# design.net
KiCad netlist of a schematic drawn in Altium Designer
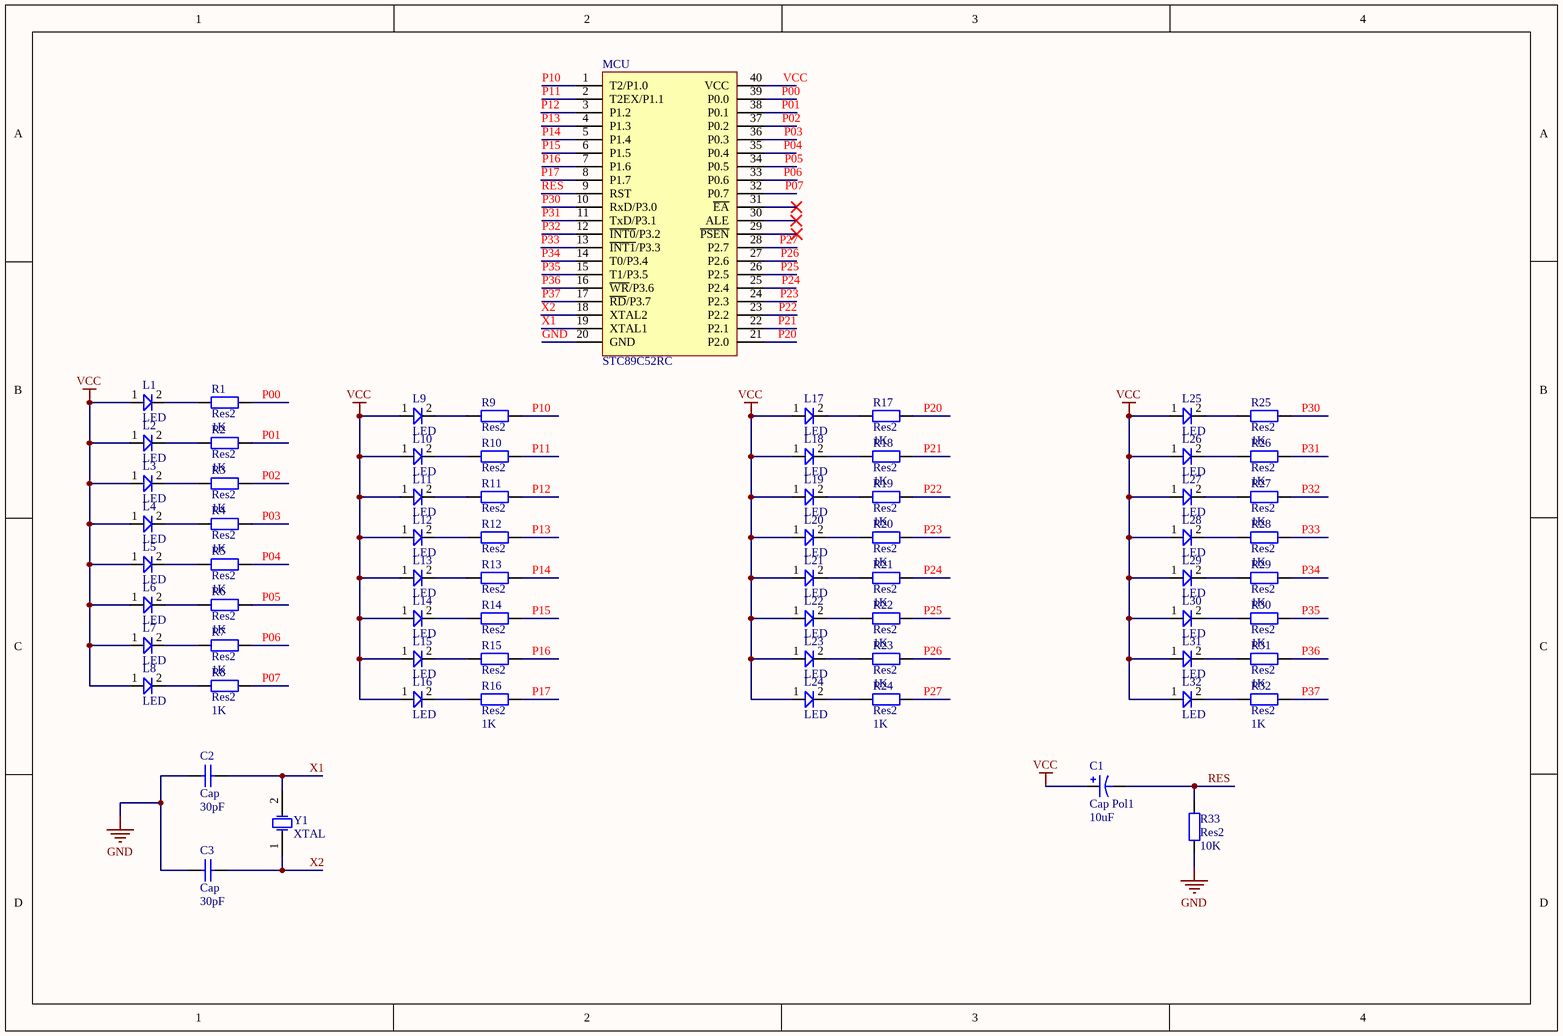
[diagram p0: 心形流水灯原理图.SchDoc]

(export (version "E")
  (design (tool "Eeschema 10.0.6"))
  (components
    (comp (ref "C1")
      (value "Cap Pol1")
      (footprint "CAP-SMD_BD5.0-L5.3-W5.3-FD")
      (description "Polarized Capacitor (Radial)")
      (fields (field (name "ALTIUM_VALUE") "10uF") (field (name "PUBLISHER") "Altium Limited"))
      (libsource (lib "Miscellaneous Devices") (part "Cap Pol1"))
    )
    (comp (ref "C2")
      (value "Cap")
      (footprint "C0603")
      (description "Capacitor")
      (fields (field (name "ALTIUM_VALUE") "30pF") (field (name "PUBLISHER") "Altium Limited"))
      (libsource (lib "Miscellaneous Devices") (part "Cap"))
    )
    (comp (ref "C3")
      (value "Cap")
      (footprint "C0603")
      (description "Capacitor")
      (fields (field (name "ALTIUM_VALUE") "30pF") (field (name "PUBLISHER") "Altium Limited"))
      (libsource (lib "Miscellaneous Devices") (part "Cap"))
    )
    (comp (ref "L1")
      (value "LED")
      (footprint "LED-TH_BD5.6-P2.54-FD")
      (libsource (lib "XIACHUN") (part "LED_T"))
    )
    (comp (ref "L2")
      (value "LED")
      (footprint "LED-TH_BD5.6-P2.54-FD")
      (libsource (lib "XIACHUN") (part "LED_T"))
    )
    (comp (ref "L3")
      (value "LED")
      (footprint "LED-TH_BD5.6-P2.54-FD")
      (libsource (lib "XIACHUN") (part "LED_T"))
    )
    (comp (ref "L4")
      (value "LED")
      (footprint "LED-TH_BD5.6-P2.54-FD")
      (libsource (lib "XIACHUN") (part "LED_T"))
    )
    (comp (ref "L5")
      (value "LED")
      (footprint "LED-TH_BD5.6-P2.54-FD")
      (libsource (lib "XIACHUN") (part "LED_T"))
    )
    (comp (ref "L6")
      (value "LED")
      (footprint "LED-TH_BD5.6-P2.54-FD")
      (libsource (lib "XIACHUN") (part "LED_T"))
    )
    (comp (ref "L7")
      (value "LED")
      (footprint "LED-TH_BD5.6-P2.54-FD")
      (libsource (lib "XIACHUN") (part "LED_T"))
    )
    (comp (ref "L8")
      (value "LED")
      (footprint "LED-TH_BD5.6-P2.54-FD")
      (libsource (lib "XIACHUN") (part "LED_T"))
    )
    (comp (ref "L9")
      (value "LED")
      (footprint "LED-TH_BD5.6-P2.54-FD")
      (libsource (lib "XIACHUN") (part "LED_T"))
    )
    (comp (ref "L10")
      (value "LED")
      (footprint "LED-TH_BD5.6-P2.54-FD")
      (libsource (lib "XIACHUN") (part "LED_T"))
    )
    (comp (ref "L11")
      (value "LED")
      (footprint "LED-TH_BD5.6-P2.54-FD")
      (libsource (lib "XIACHUN") (part "LED_T"))
    )
    (comp (ref "L12")
      (value "LED")
      (footprint "LED-TH_BD5.6-P2.54-FD")
      (libsource (lib "XIACHUN") (part "LED_T"))
    )
    (comp (ref "L13")
      (value "LED")
      (footprint "LED-TH_BD5.6-P2.54-FD")
      (libsource (lib "XIACHUN") (part "LED_T"))
    )
    (comp (ref "L14")
      (value "LED")
      (footprint "LED-TH_BD5.6-P2.54-FD")
      (libsource (lib "XIACHUN") (part "LED_T"))
    )
    (comp (ref "L15")
      (value "LED")
      (footprint "LED-TH_BD5.6-P2.54-FD")
      (libsource (lib "XIACHUN") (part "LED_T"))
    )
    (comp (ref "L16")
      (value "LED")
      (footprint "LED-TH_BD5.6-P2.54-FD")
      (libsource (lib "XIACHUN") (part "LED_T"))
    )
    (comp (ref "L17")
      (value "LED")
      (footprint "LED-TH_BD5.6-P2.54-FD")
      (libsource (lib "XIACHUN") (part "LED_T"))
    )
    (comp (ref "L18")
      (value "LED")
      (footprint "LED-TH_BD5.6-P2.54-FD")
      (libsource (lib "XIACHUN") (part "LED_T"))
    )
    (comp (ref "L19")
      (value "LED")
      (footprint "LED-TH_BD5.6-P2.54-FD")
      (libsource (lib "XIACHUN") (part "LED_T"))
    )
    (comp (ref "L20")
      (value "LED")
      (footprint "LED-TH_BD5.6-P2.54-FD")
      (libsource (lib "XIACHUN") (part "LED_T"))
    )
    (comp (ref "L21")
      (value "LED")
      (footprint "LED-TH_BD5.6-P2.54-FD")
      (libsource (lib "XIACHUN") (part "LED_T"))
    )
    (comp (ref "L22")
      (value "LED")
      (footprint "LED-TH_BD5.6-P2.54-FD")
      (libsource (lib "XIACHUN") (part "LED_T"))
    )
    (comp (ref "L23")
      (value "LED")
      (footprint "LED-TH_BD5.6-P2.54-FD")
      (libsource (lib "XIACHUN") (part "LED_T"))
    )
    (comp (ref "L24")
      (value "LED")
      (footprint "LED-TH_BD5.6-P2.54-FD")
      (libsource (lib "XIACHUN") (part "LED_T"))
    )
    (comp (ref "L25")
      (value "LED")
      (footprint "LED-TH_BD5.6-P2.54-FD")
      (libsource (lib "XIACHUN") (part "LED_T"))
    )
    (comp (ref "L26")
      (value "LED")
      (footprint "LED-TH_BD5.6-P2.54-FD")
      (libsource (lib "XIACHUN") (part "LED_T"))
    )
    (comp (ref "L27")
      (value "LED")
      (footprint "LED-TH_BD5.6-P2.54-FD")
      (libsource (lib "XIACHUN") (part "LED_T"))
    )
    (comp (ref "L28")
      (value "LED")
      (footprint "LED-TH_BD5.6-P2.54-FD")
      (libsource (lib "XIACHUN") (part "LED_T"))
    )
    (comp (ref "L29")
      (value "LED")
      (footprint "LED-TH_BD5.6-P2.54-FD")
      (libsource (lib "XIACHUN") (part "LED_T"))
    )
    (comp (ref "L30")
      (value "LED")
      (footprint "LED-TH_BD5.6-P2.54-FD")
      (libsource (lib "XIACHUN") (part "LED_T"))
    )
    (comp (ref "L31")
      (value "LED")
      (footprint "LED-TH_BD5.6-P2.54-FD")
      (libsource (lib "XIACHUN") (part "LED_T"))
    )
    (comp (ref "L32")
      (value "LED")
      (footprint "LED-TH_BD5.6-P2.54-FD")
      (libsource (lib "XIACHUN") (part "LED_T"))
    )
    (comp (ref "MCU")
      (value "STC89C52RC")
      (footprint "DIP-40_L50.8-W17.8-P2.54-LS15.2-BL")
      (description "STC单片机")
      (fields (field (name "版权归属") "源创客"))
      (libsource (lib "STC系列单片机") (part "STC89C52RC"))
    )
    (comp (ref "R1")
      (value "Res2")
      (footprint "R0603")
      (description "Resistor")
      (fields (field (name "ALTIUM_VALUE") "1K") (field (name "PUBLISHER") "Altium Limited"))
      (libsource (lib "Miscellaneous Devices") (part "Res2"))
    )
    (comp (ref "R2")
      (value "Res2")
      (footprint "R0603")
      (description "Resistor")
      (fields (field (name "ALTIUM_VALUE") "1K") (field (name "PUBLISHER") "Altium Limited"))
      (libsource (lib "Miscellaneous Devices") (part "Res2"))
    )
    (comp (ref "R3")
      (value "Res2")
      (footprint "R0603")
      (description "Resistor")
      (fields (field (name "ALTIUM_VALUE") "1K") (field (name "PUBLISHER") "Altium Limited"))
      (libsource (lib "Miscellaneous Devices") (part "Res2"))
    )
    (comp (ref "R4")
      (value "Res2")
      (footprint "R0603")
      (description "Resistor")
      (fields (field (name "ALTIUM_VALUE") "1K") (field (name "PUBLISHER") "Altium Limited"))
      (libsource (lib "Miscellaneous Devices") (part "Res2"))
    )
    (comp (ref "R5")
      (value "Res2")
      (footprint "R0603")
      (description "Resistor")
      (fields (field (name "ALTIUM_VALUE") "1K") (field (name "PUBLISHER") "Altium Limited"))
      (libsource (lib "Miscellaneous Devices") (part "Res2"))
    )
    (comp (ref "R6")
      (value "Res2")
      (footprint "R0603")
      (description "Resistor")
      (fields (field (name "ALTIUM_VALUE") "1K") (field (name "PUBLISHER") "Altium Limited"))
      (libsource (lib "Miscellaneous Devices") (part "Res2"))
    )
    (comp (ref "R7")
      (value "Res2")
      (footprint "R0603")
      (description "Resistor")
      (fields (field (name "ALTIUM_VALUE") "1K") (field (name "PUBLISHER") "Altium Limited"))
      (libsource (lib "Miscellaneous Devices") (part "Res2"))
    )
    (comp (ref "R8")
      (value "Res2")
      (footprint "R0603")
      (description "Resistor")
      (fields (field (name "ALTIUM_VALUE") "1K") (field (name "PUBLISHER") "Altium Limited"))
      (libsource (lib "Miscellaneous Devices") (part "Res2"))
    )
    (comp (ref "R9")
      (value "Res2")
      (footprint "R0603")
      (description "Resistor")
      (fields (field (name "PUBLISHER") "Altium Limited"))
      (libsource (lib "Miscellaneous Devices") (part "Res2"))
    )
    (comp (ref "R10")
      (value "Res2")
      (footprint "R0603")
      (description "Resistor")
      (fields (field (name "PUBLISHER") "Altium Limited"))
      (libsource (lib "Miscellaneous Devices") (part "Res2"))
    )
    (comp (ref "R11")
      (value "Res2")
      (footprint "R0603")
      (description "Resistor")
      (fields (field (name "PUBLISHER") "Altium Limited"))
      (libsource (lib "Miscellaneous Devices") (part "Res2"))
    )
    (comp (ref "R12")
      (value "Res2")
      (footprint "R0603")
      (description "Resistor")
      (fields (field (name "PUBLISHER") "Altium Limited"))
      (libsource (lib "Miscellaneous Devices") (part "Res2"))
    )
    (comp (ref "R13")
      (value "Res2")
      (footprint "R0603")
      (description "Resistor")
      (fields (field (name "PUBLISHER") "Altium Limited"))
      (libsource (lib "Miscellaneous Devices") (part "Res2"))
    )
    (comp (ref "R14")
      (value "Res2")
      (footprint "R0603")
      (description "Resistor")
      (fields (field (name "PUBLISHER") "Altium Limited"))
      (libsource (lib "Miscellaneous Devices") (part "Res2"))
    )
    (comp (ref "R15")
      (value "Res2")
      (footprint "R0603")
      (description "Resistor")
      (fields (field (name "PUBLISHER") "Altium Limited"))
      (libsource (lib "Miscellaneous Devices") (part "Res2"))
    )
    (comp (ref "R16")
      (value "Res2")
      (footprint "R0603")
      (description "Resistor")
      (fields (field (name "ALTIUM_VALUE") "1K") (field (name "PUBLISHER") "Altium Limited"))
      (libsource (lib "Miscellaneous Devices") (part "Res2"))
    )
    (comp (ref "R17")
      (value "Res2")
      (footprint "R0603")
      (description "Resistor")
      (fields (field (name "ALTIUM_VALUE") "1K") (field (name "PUBLISHER") "Altium Limited"))
      (libsource (lib "Miscellaneous Devices") (part "Res2"))
    )
    (comp (ref "R18")
      (value "Res2")
      (footprint "R0603")
      (description "Resistor")
      (fields (field (name "ALTIUM_VALUE") "1K") (field (name "PUBLISHER") "Altium Limited"))
      (libsource (lib "Miscellaneous Devices") (part "Res2"))
    )
    (comp (ref "R19")
      (value "Res2")
      (footprint "R0603")
      (description "Resistor")
      (fields (field (name "ALTIUM_VALUE") "1K") (field (name "PUBLISHER") "Altium Limited"))
      (libsource (lib "Miscellaneous Devices") (part "Res2"))
    )
    (comp (ref "R20")
      (value "Res2")
      (footprint "R0603")
      (description "Resistor")
      (fields (field (name "ALTIUM_VALUE") "1K") (field (name "PUBLISHER") "Altium Limited"))
      (libsource (lib "Miscellaneous Devices") (part "Res2"))
    )
    (comp (ref "R21")
      (value "Res2")
      (footprint "R0603")
      (description "Resistor")
      (fields (field (name "ALTIUM_VALUE") "1K") (field (name "PUBLISHER") "Altium Limited"))
      (libsource (lib "Miscellaneous Devices") (part "Res2"))
    )
    (comp (ref "R22")
      (value "Res2")
      (footprint "R0603")
      (description "Resistor")
      (fields (field (name "ALTIUM_VALUE") "1K") (field (name "PUBLISHER") "Altium Limited"))
      (libsource (lib "Miscellaneous Devices") (part "Res2"))
    )
    (comp (ref "R23")
      (value "Res2")
      (footprint "R0603")
      (description "Resistor")
      (fields (field (name "ALTIUM_VALUE") "1K") (field (name "PUBLISHER") "Altium Limited"))
      (libsource (lib "Miscellaneous Devices") (part "Res2"))
    )
    (comp (ref "R24")
      (value "Res2")
      (footprint "R0603")
      (description "Resistor")
      (fields (field (name "ALTIUM_VALUE") "1K") (field (name "PUBLISHER") "Altium Limited"))
      (libsource (lib "Miscellaneous Devices") (part "Res2"))
    )
    (comp (ref "R25")
      (value "Res2")
      (footprint "R0603")
      (description "Resistor")
      (fields (field (name "ALTIUM_VALUE") "1K") (field (name "PUBLISHER") "Altium Limited"))
      (libsource (lib "Miscellaneous Devices") (part "Res2"))
    )
    (comp (ref "R26")
      (value "Res2")
      (footprint "R0603")
      (description "Resistor")
      (fields (field (name "ALTIUM_VALUE") "1K") (field (name "PUBLISHER") "Altium Limited"))
      (libsource (lib "Miscellaneous Devices") (part "Res2"))
    )
    (comp (ref "R27")
      (value "Res2")
      (footprint "R0603")
      (description "Resistor")
      (fields (field (name "ALTIUM_VALUE") "1K") (field (name "PUBLISHER") "Altium Limited"))
      (libsource (lib "Miscellaneous Devices") (part "Res2"))
    )
    (comp (ref "R28")
      (value "Res2")
      (footprint "R0603")
      (description "Resistor")
      (fields (field (name "ALTIUM_VALUE") "1K") (field (name "PUBLISHER") "Altium Limited"))
      (libsource (lib "Miscellaneous Devices") (part "Res2"))
    )
    (comp (ref "R29")
      (value "Res2")
      (footprint "R0603")
      (description "Resistor")
      (fields (field (name "ALTIUM_VALUE") "1K") (field (name "PUBLISHER") "Altium Limited"))
      (libsource (lib "Miscellaneous Devices") (part "Res2"))
    )
    (comp (ref "R30")
      (value "Res2")
      (footprint "R0603")
      (description "Resistor")
      (fields (field (name "ALTIUM_VALUE") "1K") (field (name "PUBLISHER") "Altium Limited"))
      (libsource (lib "Miscellaneous Devices") (part "Res2"))
    )
    (comp (ref "R31")
      (value "Res2")
      (footprint "R0603")
      (description "Resistor")
      (fields (field (name "ALTIUM_VALUE") "1K") (field (name "PUBLISHER") "Altium Limited"))
      (libsource (lib "Miscellaneous Devices") (part "Res2"))
    )
    (comp (ref "R32")
      (value "Res2")
      (footprint "R0603")
      (description "Resistor")
      (fields (field (name "ALTIUM_VALUE") "1K") (field (name "PUBLISHER") "Altium Limited"))
      (libsource (lib "Miscellaneous Devices") (part "Res2"))
    )
    (comp (ref "R33")
      (value "Res2")
      (footprint "R0603")
      (description "Resistor")
      (fields (field (name "ALTIUM_VALUE") "10K") (field (name "PUBLISHER") "Altium Limited"))
      (libsource (lib "") (part "Res2_1"))
    )
    (comp (ref "Y1")
      (value "XTAL")
      (footprint "HC-49S_L11.4-W4.8")
      (description "Crystal Oscillator")
      (fields (field (name "PUBLISHER") "Altium Limited"))
      (libsource (lib "Miscellaneous Devices") (part "XTAL"))
    )
  )
  (nets
    (net (code "1") (name "/P00") (class "Default")
      (node (ref "MCU") (pin "39") (pinfunction "P0.0_39") (pintype "passive"))
      (node (ref "R1") (pin "2") (pinfunction "2_2") (pintype "passive"))
    )
    (net (code "2") (name "/P01") (class "Default")
      (node (ref "MCU") (pin "38") (pinfunction "P0.1_38") (pintype "passive"))
      (node (ref "R2") (pin "2") (pinfunction "2_2") (pintype "passive"))
    )
    (net (code "3") (name "/P02") (class "Default")
      (node (ref "MCU") (pin "37") (pinfunction "P0.2_37") (pintype "passive"))
      (node (ref "R3") (pin "2") (pinfunction "2_2") (pintype "passive"))
    )
    (net (code "4") (name "/P03") (class "Default")
      (node (ref "MCU") (pin "36") (pinfunction "P0.3_36") (pintype "passive"))
      (node (ref "R4") (pin "2") (pinfunction "2_2") (pintype "passive"))
    )
    (net (code "5") (name "/P04") (class "Default")
      (node (ref "MCU") (pin "35") (pinfunction "P0.4_35") (pintype "passive"))
      (node (ref "R5") (pin "2") (pinfunction "2_2") (pintype "passive"))
    )
    (net (code "6") (name "/P05") (class "Default")
      (node (ref "MCU") (pin "34") (pinfunction "P0.5_34") (pintype "passive"))
      (node (ref "R6") (pin "2") (pinfunction "2_2") (pintype "passive"))
    )
    (net (code "7") (name "/P06") (class "Default")
      (node (ref "MCU") (pin "33") (pinfunction "P0.6_33") (pintype "passive"))
      (node (ref "R7") (pin "2") (pinfunction "2_2") (pintype "passive"))
    )
    (net (code "8") (name "/P07") (class "Default")
      (node (ref "MCU") (pin "32") (pinfunction "P0.7_32") (pintype "passive"))
      (node (ref "R8") (pin "2") (pinfunction "2_2") (pintype "passive"))
    )
    (net (code "9") (name "/P10") (class "Default")
      (node (ref "MCU") (pin "1") (pinfunction "T2/P1.0_1") (pintype "passive"))
      (node (ref "R9") (pin "2") (pinfunction "2_2") (pintype "passive"))
    )
    (net (code "10") (name "/P11") (class "Default")
      (node (ref "MCU") (pin "2") (pinfunction "T2EX/P1.1_2") (pintype "passive"))
      (node (ref "R10") (pin "2") (pinfunction "2_2") (pintype "passive"))
    )
    (net (code "11") (name "/P12") (class "Default")
      (node (ref "MCU") (pin "3") (pinfunction "P1.2_3") (pintype "passive"))
      (node (ref "R11") (pin "2") (pinfunction "2_2") (pintype "passive"))
    )
    (net (code "12") (name "/P13") (class "Default")
      (node (ref "MCU") (pin "4") (pinfunction "P1.3_4") (pintype "passive"))
      (node (ref "R12") (pin "2") (pinfunction "2_2") (pintype "passive"))
    )
    (net (code "13") (name "/P14") (class "Default")
      (node (ref "MCU") (pin "5") (pinfunction "P1.4_5") (pintype "passive"))
      (node (ref "R13") (pin "2") (pinfunction "2_2") (pintype "passive"))
    )
    (net (code "14") (name "/P15") (class "Default")
      (node (ref "MCU") (pin "6") (pinfunction "P1.5_6") (pintype "passive"))
      (node (ref "R14") (pin "2") (pinfunction "2_2") (pintype "passive"))
    )
    (net (code "15") (name "/P16") (class "Default")
      (node (ref "MCU") (pin "7") (pinfunction "P1.6_7") (pintype "passive"))
      (node (ref "R15") (pin "2") (pinfunction "2_2") (pintype "passive"))
    )
    (net (code "16") (name "/P17") (class "Default")
      (node (ref "MCU") (pin "8") (pinfunction "P1.7_8") (pintype "passive"))
      (node (ref "R16") (pin "2") (pinfunction "2_2") (pintype "passive"))
    )
    (net (code "17") (name "/P20") (class "Default")
      (node (ref "MCU") (pin "21") (pinfunction "P2.0_21") (pintype "passive"))
      (node (ref "R17") (pin "2") (pinfunction "2_2") (pintype "passive"))
    )
    (net (code "18") (name "/P21") (class "Default")
      (node (ref "MCU") (pin "22") (pinfunction "P2.1_22") (pintype "passive"))
      (node (ref "R18") (pin "2") (pinfunction "2_2") (pintype "passive"))
    )
    (net (code "19") (name "/P22") (class "Default")
      (node (ref "MCU") (pin "23") (pinfunction "P2.2_23") (pintype "passive"))
      (node (ref "R19") (pin "2") (pinfunction "2_2") (pintype "passive"))
    )
    (net (code "20") (name "/P23") (class "Default")
      (node (ref "MCU") (pin "24") (pinfunction "P2.3_24") (pintype "passive"))
      (node (ref "R20") (pin "2") (pinfunction "2_2") (pintype "passive"))
    )
    (net (code "21") (name "/P24") (class "Default")
      (node (ref "MCU") (pin "25") (pinfunction "P2.4_25") (pintype "passive"))
      (node (ref "R21") (pin "2") (pinfunction "2_2") (pintype "passive"))
    )
    (net (code "22") (name "/P25") (class "Default")
      (node (ref "MCU") (pin "26") (pinfunction "P2.5_26") (pintype "passive"))
      (node (ref "R22") (pin "2") (pinfunction "2_2") (pintype "passive"))
    )
    (net (code "23") (name "/P26") (class "Default")
      (node (ref "MCU") (pin "27") (pinfunction "P2.6_27") (pintype "passive"))
      (node (ref "R23") (pin "2") (pinfunction "2_2") (pintype "passive"))
    )
    (net (code "24") (name "/P27") (class "Default")
      (node (ref "MCU") (pin "28") (pinfunction "P2.7_28") (pintype "passive"))
      (node (ref "R24") (pin "2") (pinfunction "2_2") (pintype "passive"))
    )
    (net (code "25") (name "/P30") (class "Default")
      (node (ref "MCU") (pin "10") (pinfunction "RxD/P3.0_10") (pintype "passive"))
      (node (ref "R25") (pin "2") (pinfunction "2_2") (pintype "passive"))
    )
    (net (code "26") (name "/P31") (class "Default")
      (node (ref "MCU") (pin "11") (pinfunction "TxD/P3.1_11") (pintype "passive"))
      (node (ref "R26") (pin "2") (pinfunction "2_2") (pintype "passive"))
    )
    (net (code "27") (name "/P32") (class "Default")
      (node (ref "MCU") (pin "12") (pinfunction "~{INT0}/P3.2_12") (pintype "passive"))
      (node (ref "R27") (pin "2") (pinfunction "2_2") (pintype "passive"))
    )
    (net (code "28") (name "/P33") (class "Default")
      (node (ref "MCU") (pin "13") (pinfunction "~{INT1}/P3.3_13") (pintype "passive"))
      (node (ref "R28") (pin "2") (pinfunction "2_2") (pintype "passive"))
    )
    (net (code "29") (name "/P34") (class "Default")
      (node (ref "MCU") (pin "14") (pinfunction "T0/P3.4_14") (pintype "passive"))
      (node (ref "R29") (pin "2") (pinfunction "2_2") (pintype "passive"))
    )
    (net (code "30") (name "/P35") (class "Default")
      (node (ref "MCU") (pin "15") (pinfunction "T1/P3.5_15") (pintype "passive"))
      (node (ref "R30") (pin "2") (pinfunction "2_2") (pintype "passive"))
    )
    (net (code "31") (name "/P36") (class "Default")
      (node (ref "MCU") (pin "16") (pinfunction "~{WR}/P3.6_16") (pintype "passive"))
      (node (ref "R31") (pin "2") (pinfunction "2_2") (pintype "passive"))
    )
    (net (code "32") (name "/P37") (class "Default")
      (node (ref "MCU") (pin "17") (pinfunction "~{RD}/P3.7_17") (pintype "passive"))
      (node (ref "R32") (pin "2") (pinfunction "2_2") (pintype "passive"))
    )
    (net (code "33") (name "/RES") (class "Default")
      (node (ref "C1") (pin "2") (pinfunction "2_2") (pintype "passive"))
      (node (ref "MCU") (pin "9") (pinfunction "RST_9") (pintype "passive"))
      (node (ref "R33") (pin "2") (pinfunction "2_2") (pintype "passive"))
    )
    (net (code "34") (name "/X1") (class "Default")
      (node (ref "C2") (pin "2") (pinfunction "2_2") (pintype "passive"))
      (node (ref "MCU") (pin "19") (pinfunction "XTAL1_19") (pintype "passive"))
      (node (ref "Y1") (pin "2") (pinfunction "OSC2_2") (pintype "passive"))
    )
    (net (code "35") (name "/X2") (class "Default")
      (node (ref "C3") (pin "2") (pinfunction "2_2") (pintype "passive"))
      (node (ref "MCU") (pin "18") (pinfunction "XTAL2_18") (pintype "passive"))
      (node (ref "Y1") (pin "1") (pinfunction "OSC1_1") (pintype "passive"))
    )
    (net (code "36") (name "GND") (class "Default")
      (node (ref "C2") (pin "1") (pinfunction "1_1") (pintype "passive"))
      (node (ref "C3") (pin "1") (pinfunction "1_1") (pintype "passive"))
      (node (ref "MCU") (pin "20") (pinfunction "GND_20") (pintype "passive"))
      (node (ref "R33") (pin "1") (pinfunction "1_1") (pintype "passive"))
    )
    (net (code "37") (name "Net-(L1-Pad2)") (class "Default")
      (node (ref "L1") (pin "2") (pinfunction "2_2") (pintype "passive"))
      (node (ref "R1") (pin "1") (pinfunction "1_1") (pintype "passive"))
    )
    (net (code "38") (name "Net-(L2-Pad2)") (class "Default")
      (node (ref "L2") (pin "2") (pinfunction "2_2") (pintype "passive"))
      (node (ref "R2") (pin "1") (pinfunction "1_1") (pintype "passive"))
    )
    (net (code "39") (name "Net-(L3-Pad2)") (class "Default")
      (node (ref "L3") (pin "2") (pinfunction "2_2") (pintype "passive"))
      (node (ref "R3") (pin "1") (pinfunction "1_1") (pintype "passive"))
    )
    (net (code "40") (name "Net-(L4-Pad2)") (class "Default")
      (node (ref "L4") (pin "2") (pinfunction "2_2") (pintype "passive"))
      (node (ref "R4") (pin "1") (pinfunction "1_1") (pintype "passive"))
    )
    (net (code "41") (name "Net-(L5-Pad2)") (class "Default")
      (node (ref "L5") (pin "2") (pinfunction "2_2") (pintype "passive"))
      (node (ref "R5") (pin "1") (pinfunction "1_1") (pintype "passive"))
    )
    (net (code "42") (name "Net-(L6-Pad2)") (class "Default")
      (node (ref "L6") (pin "2") (pinfunction "2_2") (pintype "passive"))
      (node (ref "R6") (pin "1") (pinfunction "1_1") (pintype "passive"))
    )
    (net (code "43") (name "Net-(L7-Pad2)") (class "Default")
      (node (ref "L7") (pin "2") (pinfunction "2_2") (pintype "passive"))
      (node (ref "R7") (pin "1") (pinfunction "1_1") (pintype "passive"))
    )
    (net (code "44") (name "Net-(L8-Pad2)") (class "Default")
      (node (ref "L8") (pin "2") (pinfunction "2_2") (pintype "passive"))
      (node (ref "R8") (pin "1") (pinfunction "1_1") (pintype "passive"))
    )
    (net (code "45") (name "Net-(L9-Pad2)") (class "Default")
      (node (ref "L9") (pin "2") (pinfunction "2_2") (pintype "passive"))
      (node (ref "R9") (pin "1") (pinfunction "1_1") (pintype "passive"))
    )
    (net (code "46") (name "Net-(L10-Pad2)") (class "Default")
      (node (ref "L10") (pin "2") (pinfunction "2_2") (pintype "passive"))
      (node (ref "R10") (pin "1") (pinfunction "1_1") (pintype "passive"))
    )
    (net (code "47") (name "Net-(L11-Pad2)") (class "Default")
      (node (ref "L11") (pin "2") (pinfunction "2_2") (pintype "passive"))
      (node (ref "R11") (pin "1") (pinfunction "1_1") (pintype "passive"))
    )
    (net (code "48") (name "Net-(L12-Pad2)") (class "Default")
      (node (ref "L12") (pin "2") (pinfunction "2_2") (pintype "passive"))
      (node (ref "R12") (pin "1") (pinfunction "1_1") (pintype "passive"))
    )
    (net (code "49") (name "Net-(L13-Pad2)") (class "Default")
      (node (ref "L13") (pin "2") (pinfunction "2_2") (pintype "passive"))
      (node (ref "R13") (pin "1") (pinfunction "1_1") (pintype "passive"))
    )
    (net (code "50") (name "Net-(L14-Pad2)") (class "Default")
      (node (ref "L14") (pin "2") (pinfunction "2_2") (pintype "passive"))
      (node (ref "R14") (pin "1") (pinfunction "1_1") (pintype "passive"))
    )
    (net (code "51") (name "Net-(L15-Pad2)") (class "Default")
      (node (ref "L15") (pin "2") (pinfunction "2_2") (pintype "passive"))
      (node (ref "R15") (pin "1") (pinfunction "1_1") (pintype "passive"))
    )
    (net (code "52") (name "Net-(L16-Pad2)") (class "Default")
      (node (ref "L16") (pin "2") (pinfunction "2_2") (pintype "passive"))
      (node (ref "R16") (pin "1") (pinfunction "1_1") (pintype "passive"))
    )
    (net (code "53") (name "Net-(L17-Pad2)") (class "Default")
      (node (ref "L17") (pin "2") (pinfunction "2_2") (pintype "passive"))
      (node (ref "R17") (pin "1") (pinfunction "1_1") (pintype "passive"))
    )
    (net (code "54") (name "Net-(L18-Pad2)") (class "Default")
      (node (ref "L18") (pin "2") (pinfunction "2_2") (pintype "passive"))
      (node (ref "R18") (pin "1") (pinfunction "1_1") (pintype "passive"))
    )
    (net (code "55") (name "Net-(L19-Pad2)") (class "Default")
      (node (ref "L19") (pin "2") (pinfunction "2_2") (pintype "passive"))
      (node (ref "R19") (pin "1") (pinfunction "1_1") (pintype "passive"))
    )
    (net (code "56") (name "Net-(L20-Pad2)") (class "Default")
      (node (ref "L20") (pin "2") (pinfunction "2_2") (pintype "passive"))
      (node (ref "R20") (pin "1") (pinfunction "1_1") (pintype "passive"))
    )
    (net (code "57") (name "Net-(L21-Pad2)") (class "Default")
      (node (ref "L21") (pin "2") (pinfunction "2_2") (pintype "passive"))
      (node (ref "R21") (pin "1") (pinfunction "1_1") (pintype "passive"))
    )
    (net (code "58") (name "Net-(L22-Pad2)") (class "Default")
      (node (ref "L22") (pin "2") (pinfunction "2_2") (pintype "passive"))
      (node (ref "R22") (pin "1") (pinfunction "1_1") (pintype "passive"))
    )
    (net (code "59") (name "Net-(L23-Pad2)") (class "Default")
      (node (ref "L23") (pin "2") (pinfunction "2_2") (pintype "passive"))
      (node (ref "R23") (pin "1") (pinfunction "1_1") (pintype "passive"))
    )
    (net (code "60") (name "Net-(L24-Pad2)") (class "Default")
      (node (ref "L24") (pin "2") (pinfunction "2_2") (pintype "passive"))
      (node (ref "R24") (pin "1") (pinfunction "1_1") (pintype "passive"))
    )
    (net (code "61") (name "Net-(L25-Pad2)") (class "Default")
      (node (ref "L25") (pin "2") (pinfunction "2_2") (pintype "passive"))
      (node (ref "R25") (pin "1") (pinfunction "1_1") (pintype "passive"))
    )
    (net (code "62") (name "Net-(L26-Pad2)") (class "Default")
      (node (ref "L26") (pin "2") (pinfunction "2_2") (pintype "passive"))
      (node (ref "R26") (pin "1") (pinfunction "1_1") (pintype "passive"))
    )
    (net (code "63") (name "Net-(L27-Pad2)") (class "Default")
      (node (ref "L27") (pin "2") (pinfunction "2_2") (pintype "passive"))
      (node (ref "R27") (pin "1") (pinfunction "1_1") (pintype "passive"))
    )
    (net (code "64") (name "Net-(L28-Pad2)") (class "Default")
      (node (ref "L28") (pin "2") (pinfunction "2_2") (pintype "passive"))
      (node (ref "R28") (pin "1") (pinfunction "1_1") (pintype "passive"))
    )
    (net (code "65") (name "Net-(L29-Pad2)") (class "Default")
      (node (ref "L29") (pin "2") (pinfunction "2_2") (pintype "passive"))
      (node (ref "R29") (pin "1") (pinfunction "1_1") (pintype "passive"))
    )
    (net (code "66") (name "Net-(L30-Pad2)") (class "Default")
      (node (ref "L30") (pin "2") (pinfunction "2_2") (pintype "passive"))
      (node (ref "R30") (pin "1") (pinfunction "1_1") (pintype "passive"))
    )
    (net (code "67") (name "Net-(L31-Pad2)") (class "Default")
      (node (ref "L31") (pin "2") (pinfunction "2_2") (pintype "passive"))
      (node (ref "R31") (pin "1") (pinfunction "1_1") (pintype "passive"))
    )
    (net (code "68") (name "Net-(L32-Pad2)") (class "Default")
      (node (ref "L32") (pin "2") (pinfunction "2_2") (pintype "passive"))
      (node (ref "R32") (pin "1") (pinfunction "1_1") (pintype "passive"))
    )
    (net (code "69") (name "VCC") (class "Default")
      (node (ref "C1") (pin "1") (pinfunction "1_1") (pintype "passive"))
      (node (ref "L1") (pin "1") (pinfunction "1_1") (pintype "passive"))
      (node (ref "L10") (pin "1") (pinfunction "1_1") (pintype "passive"))
      (node (ref "L11") (pin "1") (pinfunction "1_1") (pintype "passive"))
      (node (ref "L12") (pin "1") (pinfunction "1_1") (pintype "passive"))
      (node (ref "L13") (pin "1") (pinfunction "1_1") (pintype "passive"))
      (node (ref "L14") (pin "1") (pinfunction "1_1") (pintype "passive"))
      (node (ref "L15") (pin "1") (pinfunction "1_1") (pintype "passive"))
      (node (ref "L16") (pin "1") (pinfunction "1_1") (pintype "passive"))
      (node (ref "L17") (pin "1") (pinfunction "1_1") (pintype "passive"))
      (node (ref "L18") (pin "1") (pinfunction "1_1") (pintype "passive"))
      (node (ref "L19") (pin "1") (pinfunction "1_1") (pintype "passive"))
      (node (ref "L2") (pin "1") (pinfunction "1_1") (pintype "passive"))
      (node (ref "L20") (pin "1") (pinfunction "1_1") (pintype "passive"))
      (node (ref "L21") (pin "1") (pinfunction "1_1") (pintype "passive"))
      (node (ref "L22") (pin "1") (pinfunction "1_1") (pintype "passive"))
      (node (ref "L23") (pin "1") (pinfunction "1_1") (pintype "passive"))
      (node (ref "L24") (pin "1") (pinfunction "1_1") (pintype "passive"))
      (node (ref "L25") (pin "1") (pinfunction "1_1") (pintype "passive"))
      (node (ref "L26") (pin "1") (pinfunction "1_1") (pintype "passive"))
      (node (ref "L27") (pin "1") (pinfunction "1_1") (pintype "passive"))
      (node (ref "L28") (pin "1") (pinfunction "1_1") (pintype "passive"))
      (node (ref "L29") (pin "1") (pinfunction "1_1") (pintype "passive"))
      (node (ref "L3") (pin "1") (pinfunction "1_1") (pintype "passive"))
      (node (ref "L30") (pin "1") (pinfunction "1_1") (pintype "passive"))
      (node (ref "L31") (pin "1") (pinfunction "1_1") (pintype "passive"))
      (node (ref "L32") (pin "1") (pinfunction "1_1") (pintype "passive"))
      (node (ref "L4") (pin "1") (pinfunction "1_1") (pintype "passive"))
      (node (ref "L5") (pin "1") (pinfunction "1_1") (pintype "passive"))
      (node (ref "L6") (pin "1") (pinfunction "1_1") (pintype "passive"))
      (node (ref "L7") (pin "1") (pinfunction "1_1") (pintype "passive"))
      (node (ref "L8") (pin "1") (pinfunction "1_1") (pintype "passive"))
      (node (ref "L9") (pin "1") (pinfunction "1_1") (pintype "passive"))
      (node (ref "MCU") (pin "40") (pinfunction "VCC_40") (pintype "passive"))
    )
    (net (code "70") (name "unconnected-(MCU-ALE-Pad30)") (class "Default")
      (node (ref "MCU") (pin "30") (pinfunction "ALE_30") (pintype "passive+no_connect"))
    )
    (net (code "71") (name "unconnected-(MCU-~{EA}-Pad31)") (class "Default")
      (node (ref "MCU") (pin "31") (pinfunction "~{EA}_31") (pintype "passive+no_connect"))
    )
    (net (code "72") (name "unconnected-(MCU-~{PSEN}-Pad29)") (class "Default")
      (node (ref "MCU") (pin "29") (pinfunction "~{PSEN}_29") (pintype "passive+no_connect"))
    )
  )
)
